# SH2_-_MICROCONTROLLER.net
KiCad netlist of a schematic drawn in Altium Designer
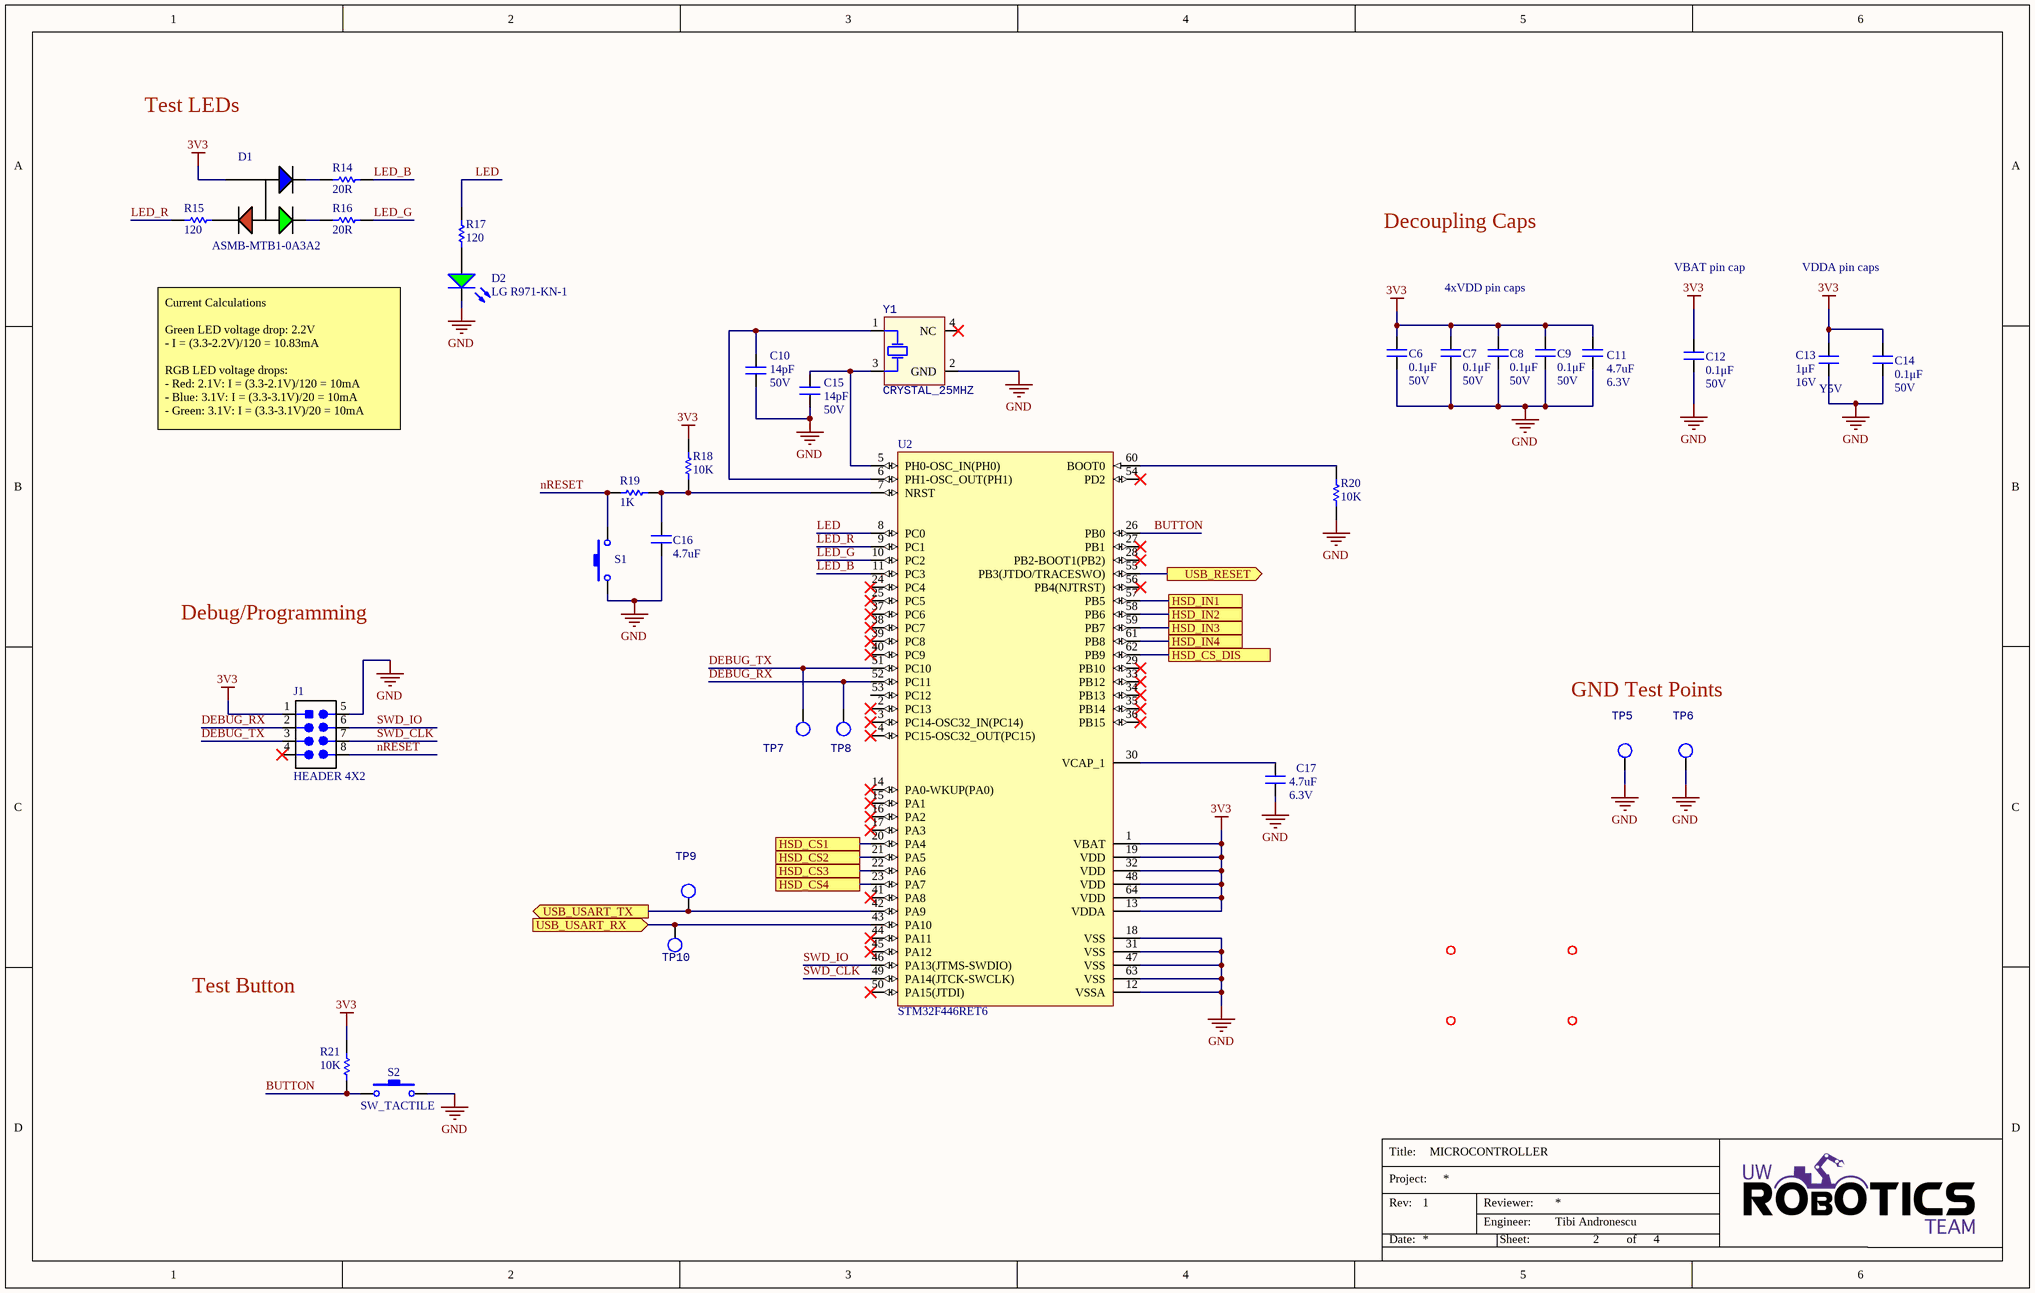
[diagram p0: SH2 - MICROCONTROLLER.SchDoc]

(export (version "E")
  (design (tool "Eeschema 10.0.6"))
  (components
    (comp (ref "C6")
      (value "0.1μF")
      (footprint "CAP2012")
      (description "CAP CER 0.1UF 50V X7R 0805")
      (fields
        (field (name "TOLERANCE") "10%")
        (field (name "VOLTAGE RATING") "50V")
        (field (name "Comment") "CAP_0.1uF_50V_0805")
      )
      (libsource (lib "UWRT_Schematic_Library_2020") (part "CAP_0.1uF_50V_0805"))
    )
    (comp (ref "C7")
      (value "0.1μF")
      (footprint "CAP2012")
      (description "CAP CER 0.1UF 50V X7R 0805")
      (fields
        (field (name "TOLERANCE") "10%")
        (field (name "VOLTAGE RATING") "50V")
        (field (name "Comment") "CAP_0.1uF_50V_0805")
      )
      (libsource (lib "UWRT_Schematic_Library_2020") (part "CAP_0.1uF_50V_0805"))
    )
    (comp (ref "C8")
      (value "0.1μF")
      (footprint "CAP2012")
      (description "CAP CER 0.1UF 50V X7R 0805")
      (fields
        (field (name "TOLERANCE") "10%")
        (field (name "VOLTAGE RATING") "50V")
        (field (name "Comment") "CAP_0.1uF_50V_0805")
      )
      (libsource (lib "UWRT_Schematic_Library_2020") (part "CAP_0.1uF_50V_0805"))
    )
    (comp (ref "C9")
      (value "0.1μF")
      (footprint "CAP2012")
      (description "CAP CER 0.1UF 50V X7R 0805")
      (fields
        (field (name "TOLERANCE") "10%")
        (field (name "VOLTAGE RATING") "50V")
        (field (name "Comment") "CAP_0.1uF_50V_0805")
      )
      (libsource (lib "UWRT_Schematic_Library_2020") (part "CAP_0.1uF_50V_0805"))
    )
    (comp (ref "C10")
      (value "14pF")
      (footprint "CAPC0603(1608)55_N")
      (description "Cap Ceramic 14pF 50V C0G 5% SMD 0603 125C Cardboard T/R")
      (fields
        (field (name "TOLERANCE") "5%")
        (field (name "VOLTAGE RATING (DC)") "50V")
        (field (name "Comment") "CL10C140JB8NNNC")
      )
      (libsource (lib "UWRT_Schematic_Library_2020") (part "CL10C140JB8NNNC"))
    )
    (comp (ref "C11")
      (value "4.7uF")
      (footprint "CAPC0603(1608)55_N")
      (description "CAP CER 4.7UF 6.3V X5R 0603")
      (fields (field (name "VOLTAGE RATING") "6.3V") (field (name "Comment") "CAP_4.7uF_0603"))
      (libsource (lib "UWRT_Schematic_Library_2020") (part "CAP_4.7uF_0603"))
    )
    (comp (ref "C12")
      (value "0.1μF")
      (footprint "CAP2012")
      (description "CAP CER 0.1UF 50V X7R 0805")
      (fields
        (field (name "TOLERANCE") "10%")
        (field (name "VOLTAGE RATING") "50V")
        (field (name "Comment") "CAP_0.1uF_50V_0805")
      )
      (libsource (lib "UWRT_Schematic_Library_2020") (part "CAP_0.1uF_50V_0805"))
    )
    (comp (ref "C13")
      (value "1μF")
      (footprint "CAP0603")
      (description "CAP CER 1UF 16V Y5V 0603")
      (fields
        (field (name "VOLTAGE RATING") "16V")
        (field (name "MANUFACTURER PART NUMBER") "CC0603ZRY5V7BB105")
        (field (name "DIELECTRIC") "Y5V")
        (field (name "Comment") "CAP_1uF_16V_0603")
      )
      (libsource (lib "UWRT_Schematic_Library_2020") (part "CAP_1uF_16V_0603"))
    )
    (comp (ref "C14")
      (value "0.1μF")
      (footprint "CAP2012")
      (description "CAP CER 0.1UF 50V X7R 0805")
      (fields
        (field (name "TOLERANCE") "10%")
        (field (name "VOLTAGE RATING") "50V")
        (field (name "Comment") "CAP_0.1uF_50V_0805")
      )
      (libsource (lib "UWRT_Schematic_Library_2020") (part "CAP_0.1uF_50V_0805"))
    )
    (comp (ref "C15")
      (value "14pF")
      (footprint "CAPC0603(1608)55_N")
      (description "Cap Ceramic 14pF 50V C0G 5% SMD 0603 125C Cardboard T/R")
      (fields
        (field (name "TOLERANCE") "5%")
        (field (name "VOLTAGE RATING (DC)") "50V")
        (field (name "Comment") "CL10C140JB8NNNC")
      )
      (libsource (lib "UWRT_Schematic_Library_2020") (part "CL10C140JB8NNNC"))
    )
    (comp (ref "C16")
      (value "4.7uF")
      (footprint "CAPC0603(1608)55_N")
      (description "CAP CER 4.7UF 6.3V X5R 0603")
      (fields (field (name "Comment") "CAP_4.7uF_0603"))
      (libsource (lib "UWRT_Schematic_Library_2020") (part "CAP_4.7uF_0603"))
    )
    (comp (ref "C17")
      (value "4.7uF")
      (footprint "CAPC0603(1608)55_N")
      (description "CAP CER 4.7UF 6.3V X5R 0603")
      (fields (field (name "VOLTAGE RATING") "6.3V") (field (name "Comment") "CAP_4.7uF_0603"))
      (libsource (lib "UWRT_Schematic_Library_2020") (part "CAP_4.7uF_0603"))
    )
    (comp (ref "D1")
      (value "LED_RGB")
      (footprint "LED_RGB")
      (description "LED RGB DIFFUSED 4PLCC SMD")
      (fields (field (name "MANUFACTURER PART NUMBER 1") "ASMB-MTB1-0A3A2"))
      (libsource (lib "UWRT_Schematic_Library_2020") (part "LED_RGB"))
    )
    (comp (ref "D2")
      (value "LG R971-KN-1")
      (footprint "LED_0805_GREEN")
      (description "LED GREEN DIFFUSED 0805 SMD")
      (libsource (lib "UWRT_Schematic_Library_2020") (part "DIO_LED_G"))
    )
    (comp (ref "J1")
      (value "HEADER 4X2")
      (footprint "HEADER_2X4")
      (description "CONN HEADER VERT 8POS 2.54MM")
      (libsource (lib "UWRT_Schematic_Library_2020") (part "HEADER 4X2"))
    )
    (comp (ref "MH1")
      (value "MOUNTING_HOLES")
      (footprint "MOUNTING_HOLE")
      (description "6cm x 6cm")
      (libsource (lib "UWRT_Schematic_Library_2020") (part "MOUNTING_HOLES"))
    )
    (comp (ref "MH2")
      (value "MOUNTING_HOLES")
      (footprint "MOUNTING_HOLE")
      (description "6cm x 6cm")
      (libsource (lib "UWRT_Schematic_Library_2020") (part "MOUNTING_HOLES"))
    )
    (comp (ref "MH3")
      (value "MOUNTING_HOLES")
      (footprint "MOUNTING_HOLE")
      (description "6cm x 6cm")
      (libsource (lib "UWRT_Schematic_Library_2020") (part "MOUNTING_HOLES"))
    )
    (comp (ref "MH4")
      (value "MOUNTING_HOLES")
      (footprint "MOUNTING_HOLE")
      (description "6cm x 6cm")
      (libsource (lib "UWRT_Schematic_Library_2020") (part "MOUNTING_HOLES"))
    )
    (comp (ref "R14")
      (value "20R")
      (footprint "RESC0603(1608)_N")
      (description "RES SMD 20 OHM 5% 1/10W 0603")
      (fields (field (name "TOLERANCE") "5%") (field (name "Comment") "RES_20R_0603"))
      (libsource (lib "UWRT_Schematic_Library_2020") (part "RES_20R_0603"))
    )
    (comp (ref "R15")
      (value "120")
      (footprint "RESC0603(1608)_N")
      (description "RES SMD 120 OHM 5% 1/10W 0603")
      (fields (field (name "TOLERANCE") "5%") (field (name "Comment") "RES_120R_0603"))
      (libsource (lib "UWRT_Schematic_Library_2020") (part "RES_120R_0603"))
    )
    (comp (ref "R16")
      (value "20R")
      (footprint "RESC0603(1608)_N")
      (description "RES SMD 20 OHM 5% 1/10W 0603")
      (fields (field (name "TOLERANCE") "5%") (field (name "Comment") "RES_20R_0603"))
      (libsource (lib "UWRT_Schematic_Library_2020") (part "RES_20R_0603"))
    )
    (comp (ref "R17")
      (value "120")
      (footprint "RESC0603(1608)_N")
      (description "RES SMD 120 OHM 5% 1/10W 0603")
      (fields (field (name "TOLERANCE") "5%") (field (name "Comment") "RES_120R_0603"))
      (libsource (lib "UWRT_Schematic_Library_2020") (part "RES_120R_0603"))
    )
    (comp (ref "R18")
      (value "10K")
      (footprint "RESC0603(1608)_N")
      (description "RES SMD 10K OHM 5% 1/10W 0603")
      (fields (field (name "TOLERANCE") "5%") (field (name "Comment") "RES_10K_0603"))
      (libsource (lib "UWRT_Schematic_Library_2020") (part "RES_10K_0603"))
    )
    (comp (ref "R19")
      (value "1K")
      (footprint "RESC0603(1608)_N")
      (description "RES SMD 1K OHM 5% 1/10W 0603")
      (fields (field (name "TOLERANCE") "5%") (field (name "Comment") "RES_1K_0603"))
      (libsource (lib "UWRT_Schematic_Library_2020") (part "RES_1K_0603"))
    )
    (comp (ref "R20")
      (value "10K")
      (footprint "RESC0603(1608)_N")
      (description "RES SMD 10K OHM 5% 1/10W 0603")
      (fields (field (name "TOLERANCE") "5%") (field (name "Comment") "RES_10K_0603"))
      (libsource (lib "UWRT_Schematic_Library_2020") (part "RES_10K_0603"))
    )
    (comp (ref "R21")
      (value "10K")
      (footprint "RESC0603(1608)_N")
      (description "RES SMD 10K OHM 5% 1/10W 0603")
      (fields (field (name "TOLERANCE") "5%") (field (name "Comment") "RES_10K_0603"))
      (libsource (lib "UWRT_Schematic_Library_2020") (part "RES_10K_0603"))
    )
    (comp (ref "S1")
      (value "SW_TACTILE")
      (footprint "B3U-1000P")
      (description "Tactile Switch (Grey)")
      (libsource (lib "UWRT_Schematic_Library_2020") (part "SW_TACTILE"))
    )
    (comp (ref "S2")
      (value "SW_TACTILE")
      (footprint "B3U-1000P")
      (description "Tactile Switch (Grey)")
      (libsource (lib "UWRT_Schematic_Library_2020") (part "SW_TACTILE"))
    )
    (comp (ref "TP5")
      (value "TESTPOINT_LOOP")
      (footprint "TESTPOINT_LOOP")
      (description "PC TEST POINT MINIATURE WHITE")
      (libsource (lib "UWRT_Schematic_Library_2020") (part "TESTPOINT_LOOP"))
    )
    (comp (ref "TP6")
      (value "TESTPOINT_LOOP")
      (footprint "TESTPOINT_LOOP")
      (description "PC TEST POINT MINIATURE WHITE")
      (libsource (lib "UWRT_Schematic_Library_2020") (part "TESTPOINT_LOOP"))
    )
    (comp (ref "TP7")
      (value "TESTPOINT_LOOP")
      (footprint "TESTPOINT_LOOP")
      (description "PC TEST POINT MINIATURE WHITE")
      (libsource (lib "UWRT_Schematic_Library_2020") (part "TESTPOINT_LOOP"))
    )
    (comp (ref "TP8")
      (value "TESTPOINT_LOOP")
      (footprint "TESTPOINT_LOOP")
      (description "PC TEST POINT MINIATURE WHITE")
      (libsource (lib "UWRT_Schematic_Library_2020") (part "TESTPOINT_LOOP"))
    )
    (comp (ref "TP9")
      (value "TESTPOINT_LOOP")
      (footprint "TESTPOINT_LOOP")
      (description "PC TEST POINT MINIATURE WHITE")
      (libsource (lib "UWRT_Schematic_Library_2020") (part "TESTPOINT_LOOP"))
    )
    (comp (ref "TP10")
      (value "TESTPOINT_LOOP")
      (footprint "TESTPOINT_LOOP")
      (description "PC TEST POINT MINIATURE WHITE")
      (libsource (lib "UWRT_Schematic_Library_2020") (part "TESTPOINT_LOOP"))
    )
    (comp (ref "U2")
      (value "STM32F446RET6")
      (footprint "STM-LQFP64_L")
      (libsource (lib "UWRT_Schematic_Library_2020") (part "MCU_STM32F446RET6"))
    )
    (comp (ref "Y1")
      (value "CRYSTAL_25MHZ")
      (footprint "SOIC254P1016X440-4N")
      (description "CRYSTAL 25.0000MHZ 12PF SMD")
      (libsource (lib "UWRT_Schematic_Library_2020") (part "CRYSTAL_25MHZ"))
    )
  )
  (nets
    (net (code "1") (name "/BUTTON") (class "Default")
      (node (ref "R21") (pin "2") (pinfunction "2_2") (pintype "passive"))
      (node (ref "S2") (pin "1") (pinfunction "1_1") (pintype "passive"))
      (node (ref "U2") (pin "26") (pinfunction "PB0_26") (pintype "bidirectional"))
    )
    (net (code "2") (name "/DEBUG_RX") (class "Default")
      (node (ref "J1") (pin "2") (pinfunction "2_2") (pintype "passive"))
      (node (ref "TP8") (pin "1") (pintype "passive"))
      (node (ref "U2") (pin "52") (pinfunction "PC11_52") (pintype "bidirectional"))
    )
    (net (code "3") (name "/DEBUG_TX") (class "Default")
      (node (ref "J1") (pin "3") (pinfunction "3_3") (pintype "passive"))
      (node (ref "TP7") (pin "1") (pintype "passive"))
      (node (ref "U2") (pin "51") (pinfunction "PC10_51") (pintype "bidirectional"))
    )
    (net (code "4") (name "/HSD_CS1") (class "Default")
      (node (ref "U2") (pin "20") (pinfunction "PA4_20") (pintype "bidirectional"))
    )
    (net (code "5") (name "/HSD_CS2") (class "Default")
      (node (ref "U2") (pin "21") (pinfunction "PA5_21") (pintype "bidirectional"))
    )
    (net (code "6") (name "/HSD_CS3") (class "Default")
      (node (ref "U2") (pin "22") (pinfunction "PA6_22") (pintype "bidirectional"))
    )
    (net (code "7") (name "/HSD_CS4") (class "Default")
      (node (ref "U2") (pin "23") (pinfunction "PA7_23") (pintype "bidirectional"))
    )
    (net (code "8") (name "/HSD_CS_DIS") (class "Default")
      (node (ref "U2") (pin "62") (pinfunction "PB9_62") (pintype "bidirectional"))
    )
    (net (code "9") (name "/HSD_IN1") (class "Default")
      (node (ref "U2") (pin "57") (pinfunction "PB5_57") (pintype "bidirectional"))
    )
    (net (code "10") (name "/HSD_IN2") (class "Default")
      (node (ref "U2") (pin "58") (pinfunction "PB6_58") (pintype "bidirectional"))
    )
    (net (code "11") (name "/HSD_IN3") (class "Default")
      (node (ref "U2") (pin "59") (pinfunction "PB7_59") (pintype "bidirectional"))
    )
    (net (code "12") (name "/HSD_IN4") (class "Default")
      (node (ref "U2") (pin "61") (pinfunction "PB8_61") (pintype "bidirectional"))
    )
    (net (code "13") (name "/LED") (class "Default")
      (node (ref "R17") (pin "1") (pinfunction "1_1") (pintype "passive"))
      (node (ref "U2") (pin "8") (pinfunction "PC0_8") (pintype "bidirectional"))
    )
    (net (code "14") (name "/LED_B") (class "Default")
      (node (ref "R14") (pin "2") (pinfunction "2_2") (pintype "passive"))
      (node (ref "U2") (pin "11") (pinfunction "PC3_11") (pintype "bidirectional"))
    )
    (net (code "15") (name "/LED_G") (class "Default")
      (node (ref "R16") (pin "2") (pinfunction "2_2") (pintype "passive"))
      (node (ref "U2") (pin "10") (pinfunction "PC2_10") (pintype "bidirectional"))
    )
    (net (code "16") (name "/LED_R") (class "Default")
      (node (ref "R15") (pin "1") (pinfunction "1_1") (pintype "passive"))
      (node (ref "U2") (pin "9") (pinfunction "PC1_9") (pintype "bidirectional"))
    )
    (net (code "17") (name "/SWD_CLK") (class "Default")
      (node (ref "J1") (pin "7") (pinfunction "3_7") (pintype "passive"))
      (node (ref "U2") (pin "49") (pinfunction "PA14(JTCK-SWCLK)_49") (pintype "bidirectional"))
    )
    (net (code "18") (name "/SWD_IO") (class "Default")
      (node (ref "J1") (pin "6") (pinfunction "2_6") (pintype "passive"))
      (node (ref "U2") (pin "46") (pinfunction "PA13(JTMS-SWDIO)_46") (pintype "bidirectional"))
    )
    (net (code "19") (name "/USB_RESET") (class "Default")
      (node (ref "U2") (pin "55") (pinfunction "PB3(JTDO/TRACESWO)_55") (pintype "bidirectional"))
    )
    (net (code "20") (name "/USB_USART_RX") (class "Default")
      (node (ref "TP10") (pin "1") (pintype "passive"))
      (node (ref "U2") (pin "43") (pinfunction "PA10_43") (pintype "bidirectional"))
    )
    (net (code "21") (name "/USB_USART_TX") (class "Default")
      (node (ref "TP9") (pin "1") (pintype "passive"))
      (node (ref "U2") (pin "42") (pinfunction "PA9_42") (pintype "bidirectional"))
    )
    (net (code "22") (name "/nRESET") (class "Default")
      (node (ref "J1") (pin "8") (pinfunction "4_8") (pintype "passive"))
      (node (ref "R19") (pin "1") (pinfunction "1_1") (pintype "passive"))
      (node (ref "S1") (pin "2") (pinfunction "2_2") (pintype "passive"))
    )
    (net (code "23") (name "3V3") (class "Default")
      (node (ref "C11") (pin "2") (pinfunction "2_2") (pintype "passive"))
      (node (ref "C12") (pin "2") (pinfunction "2_2") (pintype "passive"))
      (node (ref "C13") (pin "2") (pinfunction "2_2") (pintype "passive"))
      (node (ref "C14") (pin "2") (pinfunction "2_2") (pintype "passive"))
      (node (ref "C6") (pin "2") (pinfunction "2_2") (pintype "passive"))
      (node (ref "C7") (pin "2") (pinfunction "2_2") (pintype "passive"))
      (node (ref "C8") (pin "2") (pinfunction "2_2") (pintype "passive"))
      (node (ref "C9") (pin "2") (pinfunction "2_2") (pintype "passive"))
      (node (ref "D1") (pin "4") (pinfunction "COMMON_ANODE_4") (pintype "passive"))
      (node (ref "J1") (pin "1") (pinfunction "VCC_1") (pintype "passive"))
      (node (ref "R18") (pin "2") (pinfunction "2_2") (pintype "passive"))
      (node (ref "R21") (pin "1") (pinfunction "1_1") (pintype "passive"))
      (node (ref "U2") (pin "1") (pinfunction "VBAT_1") (pintype "power_in"))
      (node (ref "U2") (pin "13") (pinfunction "VDDA_13") (pintype "power_in"))
      (node (ref "U2") (pin "19") (pinfunction "VDD_19") (pintype "power_in"))
      (node (ref "U2") (pin "32") (pinfunction "VDD_32") (pintype "power_in"))
      (node (ref "U2") (pin "48") (pinfunction "VDD_48") (pintype "power_in"))
      (node (ref "U2") (pin "64") (pinfunction "VDD_64") (pintype "power_in"))
    )
    (net (code "24") (name "GND") (class "Default")
      (node (ref "C10") (pin "1") (pinfunction "1_1") (pintype "passive"))
      (node (ref "C11") (pin "1") (pinfunction "1_1") (pintype "passive"))
      (node (ref "C12") (pin "1") (pinfunction "1_1") (pintype "passive"))
      (node (ref "C13") (pin "1") (pinfunction "1_1") (pintype "passive"))
      (node (ref "C14") (pin "1") (pinfunction "1_1") (pintype "passive"))
      (node (ref "C15") (pin "1") (pinfunction "1_1") (pintype "passive"))
      (node (ref "C16") (pin "1") (pinfunction "1_1") (pintype "passive"))
      (node (ref "C17") (pin "1") (pinfunction "1_1") (pintype "passive"))
      (node (ref "C6") (pin "1") (pinfunction "1_1") (pintype "passive"))
      (node (ref "C7") (pin "1") (pinfunction "1_1") (pintype "passive"))
      (node (ref "C8") (pin "1") (pinfunction "1_1") (pintype "passive"))
      (node (ref "C9") (pin "1") (pinfunction "1_1") (pintype "passive"))
      (node (ref "D2") (pin "2") (pinfunction "K_2") (pintype "passive"))
      (node (ref "J1") (pin "5") (pinfunction "GND_5") (pintype "passive"))
      (node (ref "R20") (pin "2") (pinfunction "2_2") (pintype "passive"))
      (node (ref "S1") (pin "1") (pinfunction "1_1") (pintype "passive"))
      (node (ref "S2") (pin "2") (pinfunction "2_2") (pintype "passive"))
      (node (ref "TP5") (pin "1") (pintype "passive"))
      (node (ref "TP6") (pin "1") (pintype "passive"))
      (node (ref "U2") (pin "12") (pinfunction "VSSA_12") (pintype "power_in"))
      (node (ref "U2") (pin "18") (pinfunction "VSS_18") (pintype "power_in"))
      (node (ref "U2") (pin "31") (pinfunction "VSS_31") (pintype "power_in"))
      (node (ref "U2") (pin "47") (pinfunction "VSS_47") (pintype "power_in"))
      (node (ref "U2") (pin "63") (pinfunction "VSS_63") (pintype "power_in"))
      (node (ref "Y1") (pin "2") (pinfunction "GND_2") (pintype "power_in"))
    )
    (net (code "25") (name "Net-(D1-CATHODE_(BLUE))") (class "Default")
      (node (ref "D1") (pin "3") (pinfunction "CATHODE_(BLUE)_3") (pintype "passive"))
      (node (ref "R14") (pin "1") (pinfunction "1_1") (pintype "passive"))
    )
    (net (code "26") (name "Net-(D1-CATHODE_(GREEN))") (class "Default")
      (node (ref "D1") (pin "2") (pinfunction "CATHODE_(GREEN)_2") (pintype "passive"))
      (node (ref "R16") (pin "1") (pinfunction "1_1") (pintype "passive"))
    )
    (net (code "27") (name "Net-(D1-CATHODE_(RED))") (class "Default")
      (node (ref "D1") (pin "1") (pinfunction "CATHODE_(RED)_1") (pintype "passive"))
      (node (ref "R15") (pin "2") (pinfunction "2_2") (pintype "passive"))
    )
    (net (code "28") (name "Net-(D2-A)") (class "Default")
      (node (ref "D2") (pin "1") (pinfunction "A_1") (pintype "passive"))
      (node (ref "R17") (pin "2") (pinfunction "2_2") (pintype "passive"))
    )
    (net (code "29") (name "Net-(U2-BOOT0)") (class "Default")
      (node (ref "R20") (pin "1") (pinfunction "1_1") (pintype "passive"))
      (node (ref "U2") (pin "60") (pinfunction "BOOT0_60") (pintype "input"))
    )
    (net (code "30") (name "Net-(U2-NRST)") (class "Default")
      (node (ref "C16") (pin "2") (pinfunction "2_2") (pintype "passive"))
      (node (ref "R18") (pin "1") (pinfunction "1_1") (pintype "passive"))
      (node (ref "R19") (pin "2") (pinfunction "2_2") (pintype "passive"))
      (node (ref "U2") (pin "7") (pinfunction "NRST_7") (pintype "bidirectional"))
    )
    (net (code "31") (name "Net-(U2-PH0-OSC_IN(PH0))") (class "Default")
      (node (ref "C15") (pin "2") (pinfunction "2_2") (pintype "passive"))
      (node (ref "U2") (pin "5") (pinfunction "PH0-OSC_IN(PH0)_5") (pintype "bidirectional"))
      (node (ref "Y1") (pin "3") (pinfunction "HOT_3") (pintype "passive"))
    )
    (net (code "32") (name "Net-(U2-PH1-OSC_OUT(PH1))") (class "Default")
      (node (ref "C10") (pin "2") (pinfunction "2_2") (pintype "passive"))
      (node (ref "U2") (pin "6") (pinfunction "PH1-OSC_OUT(PH1)_6") (pintype "bidirectional"))
      (node (ref "Y1") (pin "1") (pinfunction "HOT_1") (pintype "passive"))
    )
    (net (code "33") (name "Net-(U2-VCAP_1)") (class "Default")
      (node (ref "C17") (pin "2") (pinfunction "2_2") (pintype "passive"))
      (node (ref "U2") (pin "30") (pinfunction "VCAP_1_30") (pintype "passive"))
    )
    (net (code "34") (name "unconnected-(J1-Pad4)") (class "Default")
      (node (ref "J1") (pin "4") (pinfunction "4_4") (pintype "passive+no_connect"))
    )
    (net (code "35") (name "unconnected-(U2-PA0-WKUP(PA0)-Pad14)") (class "Default")
      (node (ref "U2") (pin "14") (pinfunction "PA0-WKUP(PA0)_14") (pintype "bidirectional+no_connect"))
    )
    (net (code "36") (name "unconnected-(U2-PA1-Pad15)") (class "Default")
      (node (ref "U2") (pin "15") (pinfunction "PA1_15") (pintype "bidirectional+no_connect"))
    )
    (net (code "37") (name "unconnected-(U2-PA2-Pad16)") (class "Default")
      (node (ref "U2") (pin "16") (pinfunction "PA2_16") (pintype "bidirectional+no_connect"))
    )
    (net (code "38") (name "unconnected-(U2-PA3-Pad17)") (class "Default")
      (node (ref "U2") (pin "17") (pinfunction "PA3_17") (pintype "bidirectional+no_connect"))
    )
    (net (code "39") (name "unconnected-(U2-PA8-Pad41)") (class "Default")
      (node (ref "U2") (pin "41") (pinfunction "PA8_41") (pintype "bidirectional+no_connect"))
    )
    (net (code "40") (name "unconnected-(U2-PA11-Pad44)") (class "Default")
      (node (ref "U2") (pin "44") (pinfunction "PA11_44") (pintype "bidirectional+no_connect"))
    )
    (net (code "41") (name "unconnected-(U2-PA12-Pad45)") (class "Default")
      (node (ref "U2") (pin "45") (pinfunction "PA12_45") (pintype "bidirectional+no_connect"))
    )
    (net (code "42") (name "unconnected-(U2-PA15(JTDI)-Pad50)") (class "Default")
      (node (ref "U2") (pin "50") (pinfunction "PA15(JTDI)_50") (pintype "bidirectional+no_connect"))
    )
    (net (code "43") (name "unconnected-(U2-PB1-Pad27)") (class "Default")
      (node (ref "U2") (pin "27") (pinfunction "PB1_27") (pintype "bidirectional+no_connect"))
    )
    (net (code "44") (name "unconnected-(U2-PB2-BOOT1(PB2)-Pad28)") (class "Default")
      (node (ref "U2") (pin "28") (pinfunction "PB2-BOOT1(PB2)_28") (pintype "bidirectional+no_connect"))
    )
    (net (code "45") (name "unconnected-(U2-PB4(NJTRST)-Pad56)") (class "Default")
      (node (ref "U2") (pin "56") (pinfunction "PB4(NJTRST)_56") (pintype "bidirectional+no_connect"))
    )
    (net (code "46") (name "unconnected-(U2-PB10-Pad29)") (class "Default")
      (node (ref "U2") (pin "29") (pinfunction "PB10_29") (pintype "bidirectional+no_connect"))
    )
    (net (code "47") (name "unconnected-(U2-PB12-Pad33)") (class "Default")
      (node (ref "U2") (pin "33") (pinfunction "PB12_33") (pintype "bidirectional+no_connect"))
    )
    (net (code "48") (name "unconnected-(U2-PB13-Pad34)") (class "Default")
      (node (ref "U2") (pin "34") (pinfunction "PB13_34") (pintype "bidirectional+no_connect"))
    )
    (net (code "49") (name "unconnected-(U2-PB14-Pad35)") (class "Default")
      (node (ref "U2") (pin "35") (pinfunction "PB14_35") (pintype "bidirectional+no_connect"))
    )
    (net (code "50") (name "unconnected-(U2-PB15-Pad36)") (class "Default")
      (node (ref "U2") (pin "36") (pinfunction "PB15_36") (pintype "bidirectional+no_connect"))
    )
    (net (code "51") (name "unconnected-(U2-PC4-Pad24)") (class "Default")
      (node (ref "U2") (pin "24") (pinfunction "PC4_24") (pintype "bidirectional+no_connect"))
    )
    (net (code "52") (name "unconnected-(U2-PC5-Pad25)") (class "Default")
      (node (ref "U2") (pin "25") (pinfunction "PC5_25") (pintype "bidirectional+no_connect"))
    )
    (net (code "53") (name "unconnected-(U2-PC6-Pad37)") (class "Default")
      (node (ref "U2") (pin "37") (pinfunction "PC6_37") (pintype "bidirectional+no_connect"))
    )
    (net (code "54") (name "unconnected-(U2-PC7-Pad38)") (class "Default")
      (node (ref "U2") (pin "38") (pinfunction "PC7_38") (pintype "bidirectional+no_connect"))
    )
    (net (code "55") (name "unconnected-(U2-PC8-Pad39)") (class "Default")
      (node (ref "U2") (pin "39") (pinfunction "PC8_39") (pintype "bidirectional+no_connect"))
    )
    (net (code "56") (name "unconnected-(U2-PC9-Pad40)") (class "Default")
      (node (ref "U2") (pin "40") (pinfunction "PC9_40") (pintype "bidirectional+no_connect"))
    )
    (net (code "57") (name "unconnected-(U2-PC12-Pad53)") (class "Default")
      (node (ref "U2") (pin "53") (pinfunction "PC12_53") (pintype "bidirectional"))
    )
    (net (code "58") (name "unconnected-(U2-PC13-Pad2)") (class "Default")
      (node (ref "U2") (pin "2") (pinfunction "PC13_2") (pintype "bidirectional+no_connect"))
    )
    (net (code "59") (name "unconnected-(U2-PC14-OSC32_IN(PC14)-Pad3)") (class "Default")
      (node (ref "U2") (pin "3") (pinfunction "PC14-OSC32_IN(PC14)_3") (pintype "bidirectional+no_connect"))
    )
    (net (code "60") (name "unconnected-(U2-PC15-OSC32_OUT(PC15)-Pad4)") (class "Default")
      (node (ref "U2") (pin "4") (pinfunction "PC15-OSC32_OUT(PC15)_4") (pintype "bidirectional+no_connect"))
    )
    (net (code "61") (name "unconnected-(U2-PD2-Pad54)") (class "Default")
      (node (ref "U2") (pin "54") (pinfunction "PD2_54") (pintype "bidirectional+no_connect"))
    )
    (net (code "62") (name "unconnected-(Y1-NC-Pad4)") (class "Default")
      (node (ref "Y1") (pin "4") (pinfunction "NC_4") (pintype "passive+no_connect"))
    )
  )
)
